# T03_Schematic.net
KiCad netlist of a schematic drawn in EAGLE
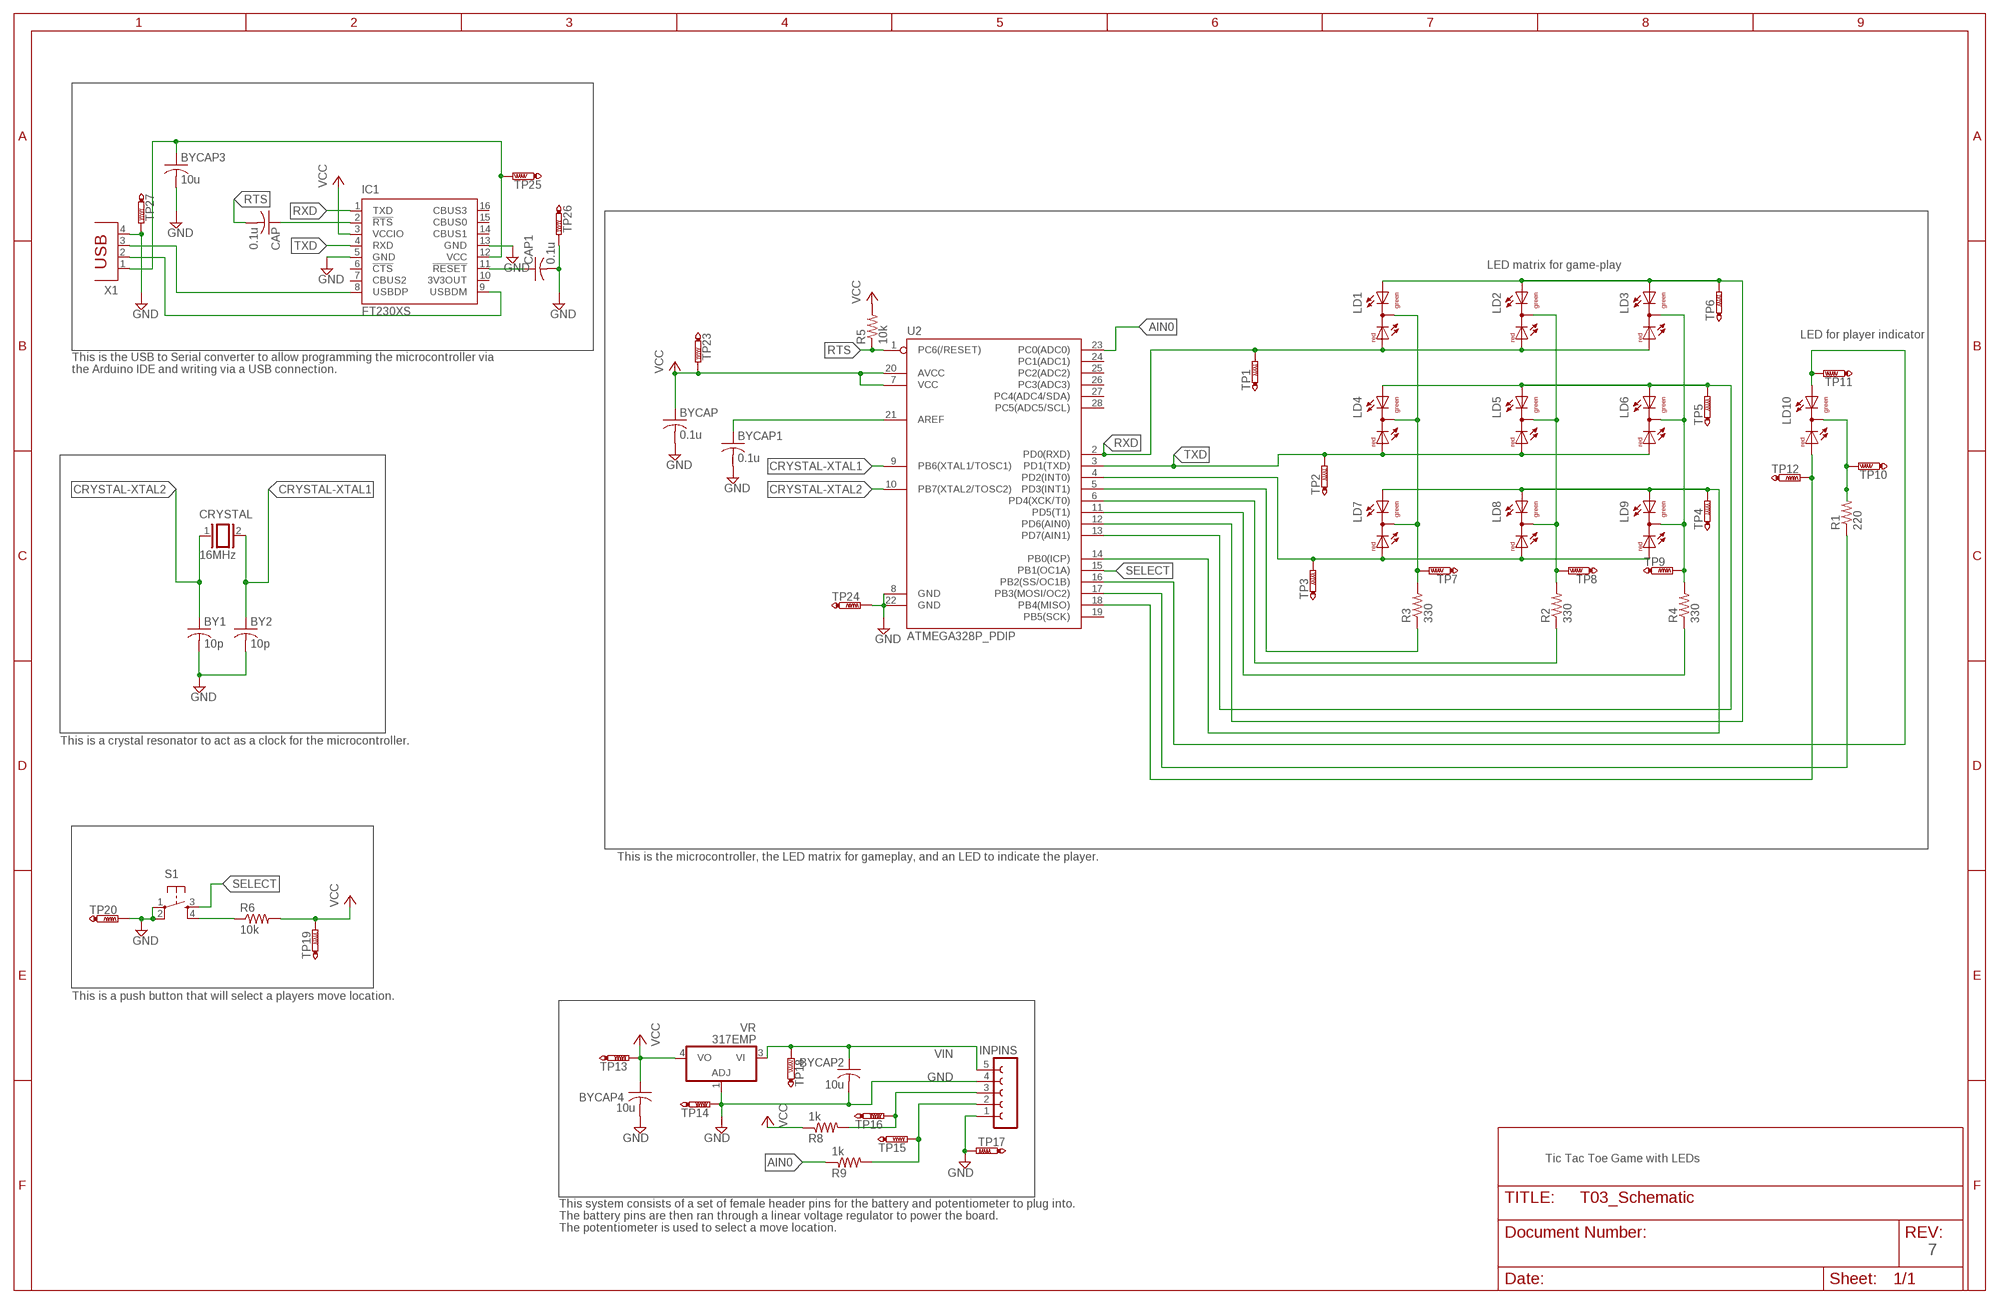
[diagram p0: schematic, sheet 1]

(export (version "E")
  (design (tool "Eeschema 10.0.6"))
  (components
    (comp (ref "BY1")
      (value "10p")
      (footprint "eagle-import:C0805")
      (libsource (lib "eagle-import") (part "C-USC0805"))
    )
    (comp (ref "BY2")
      (value "10p")
      (footprint "eagle-import:C0805")
      (libsource (lib "eagle-import") (part "C-USC0805"))
    )
    (comp (ref "BYCAP")
      (value "0.1u")
      (footprint "eagle-import:C0805")
      (libsource (lib "eagle-import") (part "C-USC0805"))
    )
    (comp (ref "BYCAP1")
      (value "0.1u")
      (footprint "eagle-import:C0805")
      (libsource (lib "eagle-import") (part "C-USC0805"))
    )
    (comp (ref "BYCAP2")
      (value "10u")
      (footprint "eagle-import:C0805")
      (libsource (lib "eagle-import") (part "C-USC0805"))
    )
    (comp (ref "BYCAP3")
      (value "10u")
      (footprint "eagle-import:C0805")
      (libsource (lib "eagle-import") (part "C-USC0805"))
    )
    (comp (ref "BYCAP4")
      (value "10u")
      (footprint "eagle-import:C0805")
      (libsource (lib "eagle-import") (part "C-USC0805"))
    )
    (comp (ref "CAP")
      (value "0.1u")
      (footprint "eagle-import:C0805")
      (libsource (lib "eagle-import") (part "C-USC0805"))
    )
    (comp (ref "CAP1")
      (value "0.1u")
      (footprint "eagle-import:C0805")
      (libsource (lib "eagle-import") (part "C-USC0805"))
    )
    (comp (ref "CRYSTAL")
      (value "16MHz")
      (footprint "eagle-import:QS")
      (libsource (lib "eagle-import") (part "XTAL/S"))
    )
    (comp (ref "IC1")
      (value "FT230XS")
      (footprint "eagle-import:SSOP16")
      (libsource (lib "eagle-import") (part "FT230XS"))
    )
    (comp (ref "INPINS")
      (value "FE05-1")
      (footprint "eagle-import:FE05-1")
      (libsource (lib "eagle-import") (part "FE05-1"))
    )
    (comp (ref "LD1")
      (value "DUOLED-RG-C")
      (footprint "eagle-import:DUOLED-C-5MM")
      (libsource (lib "eagle-import") (part "DUOLED-RG-C"))
    )
    (comp (ref "LD2")
      (value "DUOLED-RG-C")
      (footprint "eagle-import:DUOLED-C-5MM")
      (libsource (lib "eagle-import") (part "DUOLED-RG-C"))
    )
    (comp (ref "LD3")
      (value "DUOLED-RG-C")
      (footprint "eagle-import:DUOLED-C-5MM")
      (libsource (lib "eagle-import") (part "DUOLED-RG-C"))
    )
    (comp (ref "LD4")
      (value "DUOLED-RG-C")
      (footprint "eagle-import:DUOLED-C-5MM")
      (libsource (lib "eagle-import") (part "DUOLED-RG-C"))
    )
    (comp (ref "LD5")
      (value "DUOLED-RG-C")
      (footprint "eagle-import:DUOLED-C-5MM")
      (libsource (lib "eagle-import") (part "DUOLED-RG-C"))
    )
    (comp (ref "LD6")
      (value "DUOLED-RG-C")
      (footprint "eagle-import:DUOLED-C-5MM")
      (libsource (lib "eagle-import") (part "DUOLED-RG-C"))
    )
    (comp (ref "LD7")
      (value "DUOLED-RG-C")
      (footprint "eagle-import:DUOLED-C-5MM")
      (libsource (lib "eagle-import") (part "DUOLED-RG-C"))
    )
    (comp (ref "LD8")
      (value "DUOLED-RG-C")
      (footprint "eagle-import:DUOLED-C-5MM")
      (libsource (lib "eagle-import") (part "DUOLED-RG-C"))
    )
    (comp (ref "LD9")
      (value "DUOLED-RG-C")
      (footprint "eagle-import:DUOLED-C-5MM")
      (libsource (lib "eagle-import") (part "DUOLED-RG-C"))
    )
    (comp (ref "LD10")
      (value "DUOLED-RG-C")
      (footprint "eagle-import:DUOLED-C-5MM")
      (libsource (lib "eagle-import") (part "DUOLED-RG-C"))
    )
    (comp (ref "R1")
      (value "220")
      (footprint "eagle-import:M0805")
      (libsource (lib "eagle-import") (part "R-US_M0805"))
    )
    (comp (ref "R2")
      (value "330")
      (footprint "eagle-import:M0805")
      (libsource (lib "eagle-import") (part "R-US_M0805"))
    )
    (comp (ref "R3")
      (value "330")
      (footprint "eagle-import:M0805")
      (libsource (lib "eagle-import") (part "R-US_M0805"))
    )
    (comp (ref "R4")
      (value "330")
      (footprint "eagle-import:M0805")
      (libsource (lib "eagle-import") (part "R-US_M0805"))
    )
    (comp (ref "R5")
      (value "10k")
      (footprint "eagle-import:M0805")
      (libsource (lib "eagle-import") (part "R-US_M0805"))
    )
    (comp (ref "R6")
      (value "10k")
      (footprint "eagle-import:M0805")
      (libsource (lib "eagle-import") (part "R-US_M0805"))
    )
    (comp (ref "R8")
      (value "1k")
      (footprint "eagle-import:M0805")
      (libsource (lib "eagle-import") (part "R-US_M0805"))
    )
    (comp (ref "R9")
      (value "1k")
      (footprint "eagle-import:M0805")
      (libsource (lib "eagle-import") (part "R-US_M0805"))
    )
    (comp (ref "S1")
      (value "DTS-6")
      (footprint "eagle-import:DTS-6")
      (libsource (lib "eagle-import") (part "DTS-6"))
    )
    (comp (ref "TP1")
      (value "PTR1B1,27")
      (footprint "eagle-import:B1,27")
      (libsource (lib "eagle-import") (part "PTR1B1,27"))
    )
    (comp (ref "TP2")
      (value "PTR1B1,27")
      (footprint "eagle-import:B1,27")
      (libsource (lib "eagle-import") (part "PTR1B1,27"))
    )
    (comp (ref "TP3")
      (value "PTR1B1,27")
      (footprint "eagle-import:B1,27")
      (libsource (lib "eagle-import") (part "PTR1B1,27"))
    )
    (comp (ref "TP4")
      (value "PTR1B1,27")
      (footprint "eagle-import:B1,27")
      (libsource (lib "eagle-import") (part "PTR1B1,27"))
    )
    (comp (ref "TP5")
      (value "PTR1B1,27")
      (footprint "eagle-import:B1,27")
      (libsource (lib "eagle-import") (part "PTR1B1,27"))
    )
    (comp (ref "TP6")
      (value "PTR1B1,27")
      (footprint "eagle-import:B1,27")
      (libsource (lib "eagle-import") (part "PTR1B1,27"))
    )
    (comp (ref "TP7")
      (value "PTR1B1,27")
      (footprint "eagle-import:B1,27")
      (libsource (lib "eagle-import") (part "PTR1B1,27"))
    )
    (comp (ref "TP8")
      (value "PTR1B1,27")
      (footprint "eagle-import:B1,27")
      (libsource (lib "eagle-import") (part "PTR1B1,27"))
    )
    (comp (ref "TP9")
      (value "PTR1B1,27")
      (footprint "eagle-import:B1,27")
      (libsource (lib "eagle-import") (part "PTR1B1,27"))
    )
    (comp (ref "TP10")
      (value "PTR1B1,27")
      (footprint "eagle-import:B1,27")
      (libsource (lib "eagle-import") (part "PTR1B1,27"))
    )
    (comp (ref "TP11")
      (value "PTR1B1,27")
      (footprint "eagle-import:B1,27")
      (libsource (lib "eagle-import") (part "PTR1B1,27"))
    )
    (comp (ref "TP12")
      (value "PTR1B1,27")
      (footprint "eagle-import:B1,27")
      (libsource (lib "eagle-import") (part "PTR1B1,27"))
    )
    (comp (ref "TP13")
      (value "PTR1B1,27")
      (footprint "eagle-import:B1,27")
      (libsource (lib "eagle-import") (part "PTR1B1,27"))
    )
    (comp (ref "TP14")
      (value "PTR1B1,27")
      (footprint "eagle-import:B1,27")
      (libsource (lib "eagle-import") (part "PTR1B1,27"))
    )
    (comp (ref "TP15")
      (value "PTR1B1,27")
      (footprint "eagle-import:B1,27")
      (libsource (lib "eagle-import") (part "PTR1B1,27"))
    )
    (comp (ref "TP16")
      (value "PTR1B1,27")
      (footprint "eagle-import:B1,27")
      (libsource (lib "eagle-import") (part "PTR1B1,27"))
    )
    (comp (ref "TP17")
      (value "PTR1B1,27")
      (footprint "eagle-import:B1,27")
      (libsource (lib "eagle-import") (part "PTR1B1,27"))
    )
    (comp (ref "TP18")
      (value "PTR1B1,27")
      (footprint "eagle-import:B1,27")
      (libsource (lib "eagle-import") (part "PTR1B1,27"))
    )
    (comp (ref "TP19")
      (value "PTR1B1,27")
      (footprint "eagle-import:B1,27")
      (libsource (lib "eagle-import") (part "PTR1B1,27"))
    )
    (comp (ref "TP20")
      (value "PTR1B1,27")
      (footprint "eagle-import:B1,27")
      (libsource (lib "eagle-import") (part "PTR1B1,27"))
    )
    (comp (ref "TP23")
      (value "PTR1B1,27")
      (footprint "eagle-import:B1,27")
      (libsource (lib "eagle-import") (part "PTR1B1,27"))
    )
    (comp (ref "TP24")
      (value "PTR1B1,27")
      (footprint "eagle-import:B1,27")
      (libsource (lib "eagle-import") (part "PTR1B1,27"))
    )
    (comp (ref "TP25")
      (value "PTR1B1,27")
      (footprint "eagle-import:B1,27")
      (libsource (lib "eagle-import") (part "PTR1B1,27"))
    )
    (comp (ref "TP26")
      (value "PTR1B1,27")
      (footprint "eagle-import:B1,27")
      (libsource (lib "eagle-import") (part "PTR1B1,27"))
    )
    (comp (ref "TP27")
      (value "PTR1B1,27")
      (footprint "eagle-import:B1,27")
      (libsource (lib "eagle-import") (part "PTR1B1,27"))
    )
    (comp (ref "U2")
      (value "ATMEGA328P_PDIP")
      (footprint "eagle-import:DIL28-3")
      (libsource (lib "eagle-import") (part "ATMEGA328P_PDIP"))
    )
    (comp (ref "VR")
      (value "317EMP")
      (footprint "eagle-import:SOT223")
      (libsource (lib "eagle-import") (part "317EMP"))
    )
    (comp (ref "X1")
      (value "PN61729")
      (footprint "eagle-import:PN61729")
      (libsource (lib "eagle-import") (part "PN61729"))
    )
  )
  (nets
    (net (code "1") (name "/VIN") (class "Default")
      (node (ref "BYCAP2") (pin "1") (pinfunction "1_1") (pintype "passive"))
      (node (ref "INPINS") (pin "5") (pinfunction "5_5") (pintype "passive"))
      (node (ref "TP18") (pin "TP") (pinfunction "TP_TP") (pintype "input"))
      (node (ref "VR") (pin "3") (pinfunction "VI_3") (pintype "input"))
    )
    (net (code "2") (name "AIN0") (class "Default")
      (node (ref "R9") (pin "1") (pinfunction "1_1") (pintype "passive"))
      (node (ref "U2") (pin "23") (pinfunction "PC0(ADC0)_23") (pintype "bidirectional"))
    )
    (net (code "3") (name "CRYSTAL-XTAL1") (class "Default")
      (node (ref "BY2") (pin "1") (pinfunction "1_1") (pintype "passive"))
      (node (ref "CRYSTAL") (pin "2") (pinfunction "2_2") (pintype "passive"))
      (node (ref "U2") (pin "9") (pinfunction "PB6(XTAL1/TOSC1)_9") (pintype "bidirectional"))
    )
    (net (code "4") (name "CRYSTAL-XTAL2") (class "Default")
      (node (ref "BY1") (pin "1") (pinfunction "1_1") (pintype "passive"))
      (node (ref "CRYSTAL") (pin "1") (pinfunction "1_1") (pintype "passive"))
      (node (ref "U2") (pin "10") (pinfunction "PB7(XTAL2/TOSC2)_10") (pintype "bidirectional"))
    )
    (net (code "5") (name "GND") (class "Default")
      (node (ref "BY1") (pin "2") (pinfunction "2_2") (pintype "passive"))
      (node (ref "BY2") (pin "2") (pinfunction "2_2") (pintype "passive"))
      (node (ref "BYCAP") (pin "2") (pinfunction "2_2") (pintype "passive"))
      (node (ref "BYCAP1") (pin "2") (pinfunction "2_2") (pintype "passive"))
      (node (ref "BYCAP2") (pin "2") (pinfunction "2_2") (pintype "passive"))
      (node (ref "BYCAP3") (pin "2") (pinfunction "2_2") (pintype "passive"))
      (node (ref "BYCAP4") (pin "2") (pinfunction "2_2") (pintype "passive"))
      (node (ref "CAP1") (pin "2") (pinfunction "2_2") (pintype "passive"))
      (node (ref "IC1") (pin "13") (pinfunction "GND_13") (pintype "power_in"))
      (node (ref "IC1") (pin "5") (pinfunction "GND_5") (pintype "power_in"))
      (node (ref "INPINS") (pin "1") (pinfunction "1_1") (pintype "passive"))
      (node (ref "INPINS") (pin "4") (pinfunction "4_4") (pintype "passive"))
      (node (ref "S1") (pin "1") (pinfunction "1_1") (pintype "passive"))
      (node (ref "S1") (pin "2") (pinfunction "2_2") (pintype "passive"))
      (node (ref "TP14") (pin "TP") (pinfunction "TP_TP") (pintype "input"))
      (node (ref "TP17") (pin "TP") (pinfunction "TP_TP") (pintype "input"))
      (node (ref "TP20") (pin "TP") (pinfunction "TP_TP") (pintype "input"))
      (node (ref "TP24") (pin "TP") (pinfunction "TP_TP") (pintype "input"))
      (node (ref "TP26") (pin "TP") (pinfunction "TP_TP") (pintype "input"))
      (node (ref "TP27") (pin "TP") (pinfunction "TP_TP") (pintype "input"))
      (node (ref "U2") (pin "22") (pinfunction "GND_22") (pintype "bidirectional"))
      (node (ref "U2") (pin "8") (pinfunction "GND_8") (pintype "bidirectional"))
      (node (ref "VR") (pin "1") (pinfunction "ADJ_1") (pintype "input"))
      (node (ref "X1") (pin "4") (pinfunction "4_4") (pintype "passive"))
    )
    (net (code "6") (name "Net-(IC1-USBDM)") (class "Default")
      (node (ref "IC1") (pin "9") (pinfunction "USBDM_9") (pintype "input"))
      (node (ref "X1") (pin "2") (pinfunction "2_2") (pintype "passive"))
    )
    (net (code "7") (name "Net-(IC1-USBDP)") (class "Default")
      (node (ref "IC1") (pin "8") (pinfunction "USBDP_8") (pintype "input"))
      (node (ref "X1") (pin "3") (pinfunction "3_3") (pintype "passive"))
    )
    (net (code "8") (name "Net-(IC1-VCC)") (class "Default")
      (node (ref "BYCAP3") (pin "1") (pinfunction "1_1") (pintype "passive"))
      (node (ref "IC1") (pin "12") (pinfunction "VCC_12") (pintype "power_in"))
      (node (ref "TP25") (pin "TP") (pinfunction "TP_TP") (pintype "input"))
      (node (ref "X1") (pin "1") (pinfunction "1_1") (pintype "passive"))
    )
    (net (code "9") (name "Net-(IC1-~{RESET})") (class "Default")
      (node (ref "CAP1") (pin "1") (pinfunction "1_1") (pintype "passive"))
      (node (ref "IC1") (pin "11") (pinfunction "~{RESET}_11") (pintype "input"))
    )
    (net (code "10") (name "Net-(IC1-~{RTS})") (class "Default")
      (node (ref "CAP") (pin "1") (pinfunction "1_1") (pintype "passive"))
      (node (ref "IC1") (pin "2") (pinfunction "~{RTS}_2") (pintype "output"))
    )
    (net (code "11") (name "Net-(INPINS-Pad2)") (class "Default")
      (node (ref "INPINS") (pin "2") (pinfunction "2_2") (pintype "passive"))
      (node (ref "R9") (pin "2") (pinfunction "2_2") (pintype "passive"))
      (node (ref "TP15") (pin "TP") (pinfunction "TP_TP") (pintype "input"))
    )
    (net (code "12") (name "Net-(INPINS-Pad3)") (class "Default")
      (node (ref "INPINS") (pin "3") (pinfunction "3_3") (pintype "passive"))
      (node (ref "R8") (pin "2") (pinfunction "2_2") (pintype "passive"))
      (node (ref "TP16") (pin "TP") (pinfunction "TP_TP") (pintype "input"))
    )
    (net (code "13") (name "Net-(LD1-AG)") (class "Default")
      (node (ref "LD1") (pin "AX") (pinfunction "AG_AX") (pintype "passive"))
      (node (ref "LD2") (pin "AX") (pinfunction "AG_AX") (pintype "passive"))
      (node (ref "LD3") (pin "AX") (pinfunction "AG_AX") (pintype "passive"))
      (node (ref "TP6") (pin "TP") (pinfunction "TP_TP") (pintype "input"))
      (node (ref "U2") (pin "12") (pinfunction "PD6(AIN0)_12") (pintype "bidirectional"))
    )
    (net (code "14") (name "Net-(LD1-PadC)") (class "Default")
      (node (ref "LD1") (pin "C") (pinfunction "C_C") (pintype "passive"))
      (node (ref "LD4") (pin "C") (pinfunction "C_C") (pintype "passive"))
      (node (ref "LD7") (pin "C") (pinfunction "C_C") (pintype "passive"))
      (node (ref "R3") (pin "2") (pinfunction "2_2") (pintype "passive"))
      (node (ref "TP7") (pin "TP") (pinfunction "TP_TP") (pintype "input"))
    )
    (net (code "15") (name "Net-(LD2-PadC)") (class "Default")
      (node (ref "LD2") (pin "C") (pinfunction "C_C") (pintype "passive"))
      (node (ref "LD5") (pin "C") (pinfunction "C_C") (pintype "passive"))
      (node (ref "LD8") (pin "C") (pinfunction "C_C") (pintype "passive"))
      (node (ref "R2") (pin "2") (pinfunction "2_2") (pintype "passive"))
      (node (ref "TP8") (pin "TP") (pinfunction "TP_TP") (pintype "input"))
    )
    (net (code "16") (name "Net-(LD3-PadC)") (class "Default")
      (node (ref "LD3") (pin "C") (pinfunction "C_C") (pintype "passive"))
      (node (ref "LD6") (pin "C") (pinfunction "C_C") (pintype "passive"))
      (node (ref "LD9") (pin "C") (pinfunction "C_C") (pintype "passive"))
      (node (ref "R4") (pin "2") (pinfunction "2_2") (pintype "passive"))
      (node (ref "TP9") (pin "TP") (pinfunction "TP_TP") (pintype "input"))
    )
    (net (code "17") (name "Net-(LD4-AG)") (class "Default")
      (node (ref "LD4") (pin "AX") (pinfunction "AG_AX") (pintype "passive"))
      (node (ref "LD5") (pin "AX") (pinfunction "AG_AX") (pintype "passive"))
      (node (ref "LD6") (pin "AX") (pinfunction "AG_AX") (pintype "passive"))
      (node (ref "TP5") (pin "TP") (pinfunction "TP_TP") (pintype "input"))
      (node (ref "U2") (pin "13") (pinfunction "PD7(AIN1)_13") (pintype "bidirectional"))
    )
    (net (code "18") (name "Net-(LD7-AG)") (class "Default")
      (node (ref "LD7") (pin "AX") (pinfunction "AG_AX") (pintype "passive"))
      (node (ref "LD8") (pin "AX") (pinfunction "AG_AX") (pintype "passive"))
      (node (ref "LD9") (pin "AX") (pinfunction "AG_AX") (pintype "passive"))
      (node (ref "TP4") (pin "TP") (pinfunction "TP_TP") (pintype "input"))
      (node (ref "U2") (pin "14") (pinfunction "PB0(ICP)_14") (pintype "bidirectional"))
    )
    (net (code "19") (name "Net-(LD10-AG)") (class "Default")
      (node (ref "LD10") (pin "AX") (pinfunction "AG_AX") (pintype "passive"))
      (node (ref "TP11") (pin "TP") (pinfunction "TP_TP") (pintype "input"))
      (node (ref "U2") (pin "16") (pinfunction "PB2(SS/OC1B)_16") (pintype "bidirectional"))
    )
    (net (code "20") (name "Net-(LD10-PadC)") (class "Default")
      (node (ref "LD10") (pin "C") (pinfunction "C_C") (pintype "passive"))
      (node (ref "R1") (pin "2") (pinfunction "2_2") (pintype "passive"))
      (node (ref "TP10") (pin "TP") (pinfunction "TP_TP") (pintype "input"))
    )
    (net (code "21") (name "Net-(R6-Pad1)") (class "Default")
      (node (ref "R6") (pin "1") (pinfunction "1_1") (pintype "passive"))
      (node (ref "S1") (pin "4") (pinfunction "4_4") (pintype "passive"))
    )
    (net (code "22") (name "Net-(U2-AREF)") (class "Default")
      (node (ref "BYCAP1") (pin "1") (pinfunction "1_1") (pintype "passive"))
      (node (ref "U2") (pin "21") (pinfunction "AREF_21") (pintype "bidirectional"))
    )
    (net (code "23") (name "Net-(U2-PB3(MOSI{slash}OC2))") (class "Default")
      (node (ref "R1") (pin "1") (pinfunction "1_1") (pintype "passive"))
      (node (ref "U2") (pin "17") (pinfunction "PB3(MOSI/OC2)_17") (pintype "bidirectional"))
    )
    (net (code "24") (name "Net-(U2-PB4(MISO))") (class "Default")
      (node (ref "LD10") (pin "AR") (pinfunction "AR_AR") (pintype "passive"))
      (node (ref "TP12") (pin "TP") (pinfunction "TP_TP") (pintype "input"))
      (node (ref "U2") (pin "18") (pinfunction "PB4(MISO)_18") (pintype "bidirectional"))
    )
    (net (code "25") (name "Net-(U2-PD2(INT0))") (class "Default")
      (node (ref "LD7") (pin "AR") (pinfunction "AR_AR") (pintype "passive"))
      (node (ref "LD8") (pin "AR") (pinfunction "AR_AR") (pintype "passive"))
      (node (ref "LD9") (pin "AR") (pinfunction "AR_AR") (pintype "passive"))
      (node (ref "TP3") (pin "TP") (pinfunction "TP_TP") (pintype "input"))
      (node (ref "U2") (pin "4") (pinfunction "PD2(INT0)_4") (pintype "bidirectional"))
    )
    (net (code "26") (name "Net-(U2-PD3(INT1))") (class "Default")
      (node (ref "R3") (pin "1") (pinfunction "1_1") (pintype "passive"))
      (node (ref "U2") (pin "5") (pinfunction "PD3(INT1)_5") (pintype "bidirectional"))
    )
    (net (code "27") (name "Net-(U2-PD4(XCK{slash}T0))") (class "Default")
      (node (ref "R2") (pin "1") (pinfunction "1_1") (pintype "passive"))
      (node (ref "U2") (pin "6") (pinfunction "PD4(XCK/T0)_6") (pintype "bidirectional"))
    )
    (net (code "28") (name "Net-(U2-PD5(T1))") (class "Default")
      (node (ref "R4") (pin "1") (pinfunction "1_1") (pintype "passive"))
      (node (ref "U2") (pin "11") (pinfunction "PD5(T1)_11") (pintype "bidirectional"))
    )
    (net (code "29") (name "RTS") (class "Default")
      (node (ref "CAP") (pin "2") (pinfunction "2_2") (pintype "passive"))
      (node (ref "R5") (pin "1") (pinfunction "1_1") (pintype "passive"))
      (node (ref "U2") (pin "1") (pinfunction "PC6(/RESET)_1") (pintype "bidirectional"))
    )
    (net (code "30") (name "RXD") (class "Default")
      (node (ref "IC1") (pin "1") (pinfunction "TXD_1") (pintype "output"))
      (node (ref "LD1") (pin "AR") (pinfunction "AR_AR") (pintype "passive"))
      (node (ref "LD2") (pin "AR") (pinfunction "AR_AR") (pintype "passive"))
      (node (ref "LD3") (pin "AR") (pinfunction "AR_AR") (pintype "passive"))
      (node (ref "TP1") (pin "TP") (pinfunction "TP_TP") (pintype "input"))
      (node (ref "U2") (pin "2") (pinfunction "PD0(RXD)_2") (pintype "bidirectional"))
    )
    (net (code "31") (name "SELECT") (class "Default")
      (node (ref "S1") (pin "3") (pinfunction "3_3") (pintype "passive"))
      (node (ref "U2") (pin "15") (pinfunction "PB1(OC1A)_15") (pintype "bidirectional"))
    )
    (net (code "32") (name "TXD") (class "Default")
      (node (ref "IC1") (pin "4") (pinfunction "RXD_4") (pintype "input"))
      (node (ref "LD4") (pin "AR") (pinfunction "AR_AR") (pintype "passive"))
      (node (ref "LD5") (pin "AR") (pinfunction "AR_AR") (pintype "passive"))
      (node (ref "LD6") (pin "AR") (pinfunction "AR_AR") (pintype "passive"))
      (node (ref "TP2") (pin "TP") (pinfunction "TP_TP") (pintype "input"))
      (node (ref "U2") (pin "3") (pinfunction "PD1(TXD)_3") (pintype "bidirectional"))
    )
    (net (code "33") (name "VCC") (class "Default")
      (node (ref "BYCAP") (pin "1") (pinfunction "1_1") (pintype "passive"))
      (node (ref "BYCAP4") (pin "1") (pinfunction "1_1") (pintype "passive"))
      (node (ref "IC1") (pin "3") (pinfunction "VCCIO_3") (pintype "power_in"))
      (node (ref "R5") (pin "2") (pinfunction "2_2") (pintype "passive"))
      (node (ref "R6") (pin "2") (pinfunction "2_2") (pintype "passive"))
      (node (ref "R8") (pin "1") (pinfunction "1_1") (pintype "passive"))
      (node (ref "TP13") (pin "TP") (pinfunction "TP_TP") (pintype "input"))
      (node (ref "TP19") (pin "TP") (pinfunction "TP_TP") (pintype "input"))
      (node (ref "TP23") (pin "TP") (pinfunction "TP_TP") (pintype "input"))
      (node (ref "U2") (pin "20") (pinfunction "AVCC_20") (pintype "bidirectional"))
      (node (ref "U2") (pin "7") (pinfunction "VCC_7") (pintype "bidirectional"))
      (node (ref "VR") (pin "4") (pinfunction "VO_4") (pintype "passive"))
    )
    (net (code "34") (name "unconnected-(IC1-3V3OUT-Pad10)") (class "Default")
      (node (ref "IC1") (pin "10") (pinfunction "3V3OUT_10") (pintype "output"))
    )
    (net (code "35") (name "unconnected-(IC1-CBUS0-Pad15)") (class "Default")
      (node (ref "IC1") (pin "15") (pinfunction "CBUS0_15") (pintype "bidirectional"))
    )
    (net (code "36") (name "unconnected-(IC1-CBUS1-Pad14)") (class "Default")
      (node (ref "IC1") (pin "14") (pinfunction "CBUS1_14") (pintype "bidirectional"))
    )
    (net (code "37") (name "unconnected-(IC1-CBUS2-Pad7)") (class "Default")
      (node (ref "IC1") (pin "7") (pinfunction "CBUS2_7") (pintype "bidirectional"))
    )
    (net (code "38") (name "unconnected-(IC1-CBUS3-Pad16)") (class "Default")
      (node (ref "IC1") (pin "16") (pinfunction "CBUS3_16") (pintype "bidirectional"))
    )
    (net (code "39") (name "unconnected-(IC1-~{CTS}-Pad6)") (class "Default")
      (node (ref "IC1") (pin "6") (pinfunction "~{CTS}_6") (pintype "input"))
    )
    (net (code "40") (name "unconnected-(U2-PB5(SCK)-Pad19)") (class "Default")
      (node (ref "U2") (pin "19") (pinfunction "PB5(SCK)_19") (pintype "bidirectional"))
    )
    (net (code "41") (name "unconnected-(U2-PC1(ADC1)-Pad24)") (class "Default")
      (node (ref "U2") (pin "24") (pinfunction "PC1(ADC1)_24") (pintype "bidirectional"))
    )
    (net (code "42") (name "unconnected-(U2-PC2(ADC2)-Pad25)") (class "Default")
      (node (ref "U2") (pin "25") (pinfunction "PC2(ADC2)_25") (pintype "bidirectional"))
    )
    (net (code "43") (name "unconnected-(U2-PC3(ADC3)-Pad26)") (class "Default")
      (node (ref "U2") (pin "26") (pinfunction "PC3(ADC3)_26") (pintype "bidirectional"))
    )
    (net (code "44") (name "unconnected-(U2-PC4(ADC4{slash}SDA)-Pad27)") (class "Default")
      (node (ref "U2") (pin "27") (pinfunction "PC4(ADC4/SDA)_27") (pintype "bidirectional"))
    )
    (net (code "45") (name "unconnected-(U2-PC5(ADC5{slash}SCL)-Pad28)") (class "Default")
      (node (ref "U2") (pin "28") (pinfunction "PC5(ADC5/SCL)_28") (pintype "bidirectional"))
    )
  )
)
